# 08_BB_Processor.net
KiCad netlist of a schematic drawn in Altium Designer
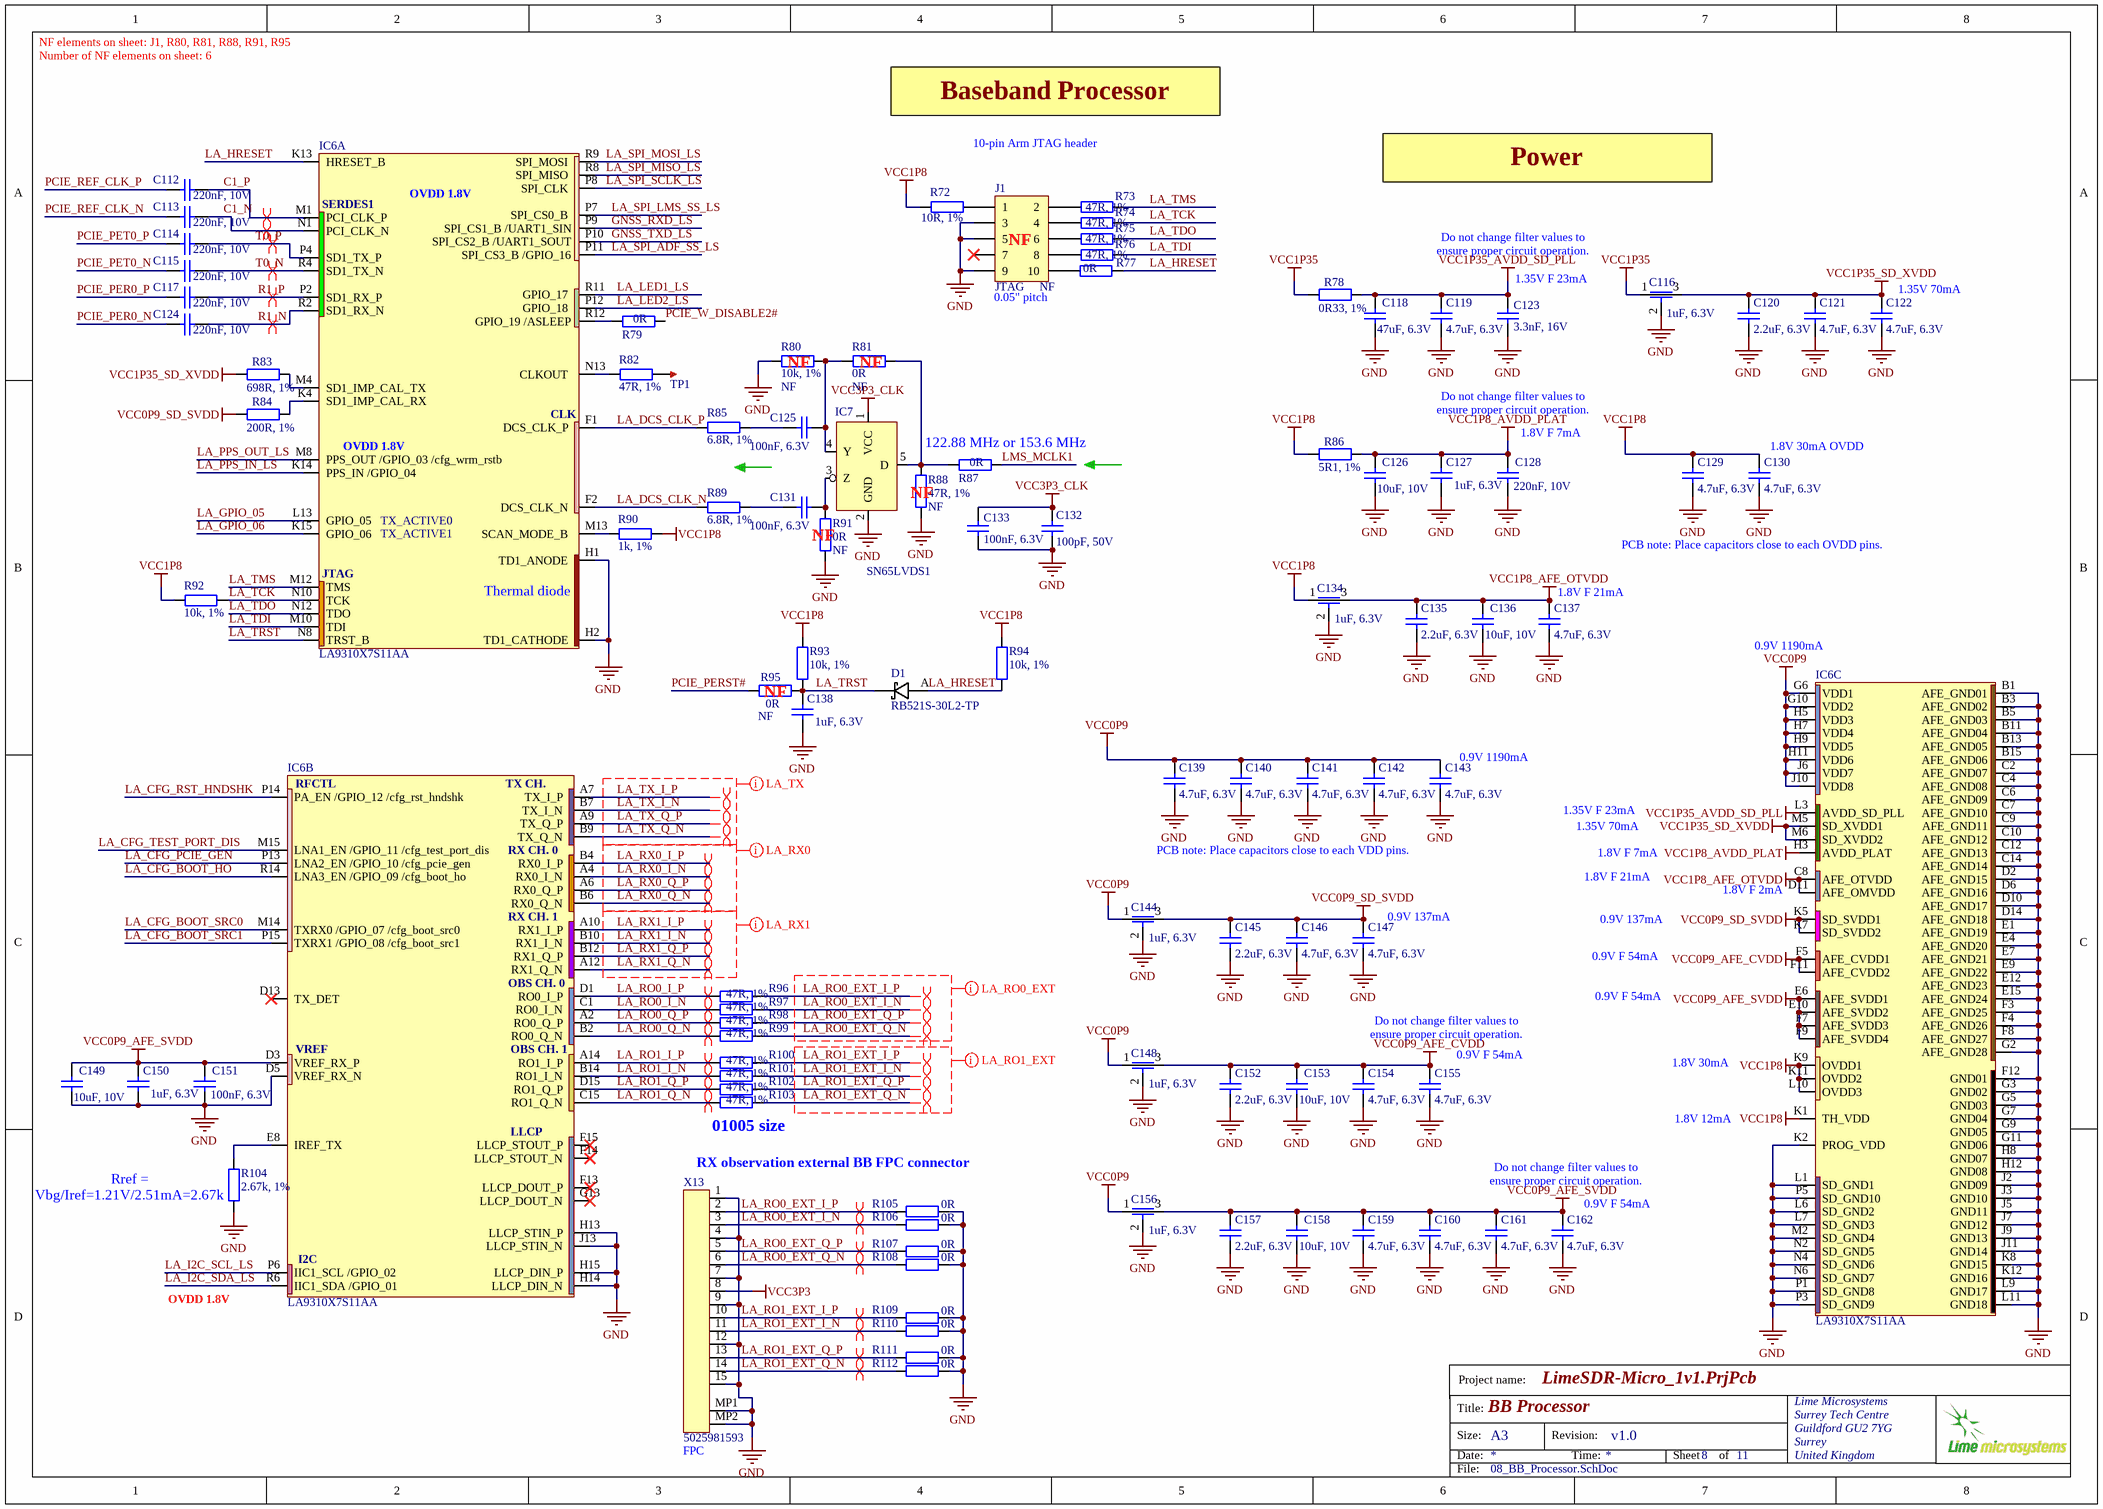
[diagram p0: 08_BB_Processor.SchDoc]

(export (version "E")
  (design (tool "Eeschema 10.0.6"))
  (components
    (comp (ref "C112")
      (value "220nF, 10V")
      (footprint "CAP0201")
      (fields
        (field (name "MANUFACTURER") "Murata")
        (field (name "TOLERANCE") "20%")
        (field (name "VOLTAGE") "10V")
      )
      (libsource (lib "LimeMicroAltiumLib_schLib") (part "Cap_0402"))
    )
    (comp (ref "C113")
      (value "220nF, 10V")
      (footprint "CAP0201")
      (fields
        (field (name "MANUFACTURER") "Murata")
        (field (name "TOLERANCE") "20%")
        (field (name "VOLTAGE") "10V")
      )
      (libsource (lib "LimeMicroAltiumLib_schLib") (part "Cap_0402"))
    )
    (comp (ref "C114")
      (value "220nF, 10V")
      (footprint "CAP0201")
      (fields
        (field (name "MANUFACTURER") "Murata")
        (field (name "TOLERANCE") "20%")
        (field (name "VOLTAGE") "10V")
      )
      (libsource (lib "LimeMicroAltiumLib_schLib") (part "Cap_0402"))
    )
    (comp (ref "C115")
      (value "220nF, 10V")
      (footprint "CAP0201")
      (fields
        (field (name "MANUFACTURER") "Murata")
        (field (name "TOLERANCE") "20%")
        (field (name "VOLTAGE") "10V")
      )
      (libsource (lib "LimeMicroAltiumLib_schLib") (part "Cap_0402"))
    )
    (comp (ref "C116")
      (value "1uF, 6.3V")
      (footprint "CAP0603_FEEDTHROUGH")
      (fields (field (name "MANUFACTURER") "TDK"))
      (libsource (lib "LimeMicroAltiumLib_schLib_r01") (part "Cap_feed_through"))
    )
    (comp (ref "C117")
      (value "220nF, 10V")
      (footprint "CAP0201")
      (fields
        (field (name "MANUFACTURER") "Murata")
        (field (name "TOLERANCE") "20%")
        (field (name "VOLTAGE") "10V")
      )
      (libsource (lib "LimeMicroAltiumLib_schLib") (part "Cap_0402"))
    )
    (comp (ref "C118")
      (value "47uF, 6.3V")
      (footprint "CAP0603")
      (fields (field (name "MANUFACTURER") "Murata") (field (name "TOLERANCE") "20%"))
      (libsource (lib "LimeFPGAboard_schLib") (part "Cap_0603"))
    )
    (comp (ref "C119")
      (value "4.7uF, 6.3V")
      (footprint "CAP0201")
      (fields (field (name "MANUFACTURER") "Murata") (field (name "TOLERANCE") "20%"))
      (libsource (lib "LimeMicroAltiumLib_schLib") (part "Cap_0402"))
    )
    (comp (ref "C120")
      (value "2.2uF, 6.3V")
      (footprint "CAP0201")
      (fields (field (name "MANUFACTURER") "Murata") (field (name "TOLERANCE") "20%"))
      (libsource (lib "LimeMicroAltiumLib_schLib") (part "Cap_0402"))
    )
    (comp (ref "C121")
      (value "4.7uF, 6.3V")
      (footprint "CAP0201")
      (fields (field (name "MANUFACTURER") "Murata") (field (name "TOLERANCE") "20%"))
      (libsource (lib "LimeMicroAltiumLib_schLib") (part "Cap_0402"))
    )
    (comp (ref "C122")
      (value "4.7uF, 6.3V")
      (footprint "CAP0201")
      (fields (field (name "MANUFACTURER") "Murata") (field (name "TOLERANCE") "20%"))
      (libsource (lib "LimeMicroAltiumLib_schLib") (part "Cap_0402"))
    )
    (comp (ref "C123")
      (value "3.3nF, 16V")
      (footprint "CAP0201")
      (description "Multilayer Ceramic Capacitor, 3300 pF, 16 V, ± 10%, X7R, 0201 [0603 Metric]")
      (fields (field (name "MANUFACTURER") "Murata"))
      (libsource (lib "LimeMicroAltiumLib_schLib") (part "Cap_0402"))
    )
    (comp (ref "C124")
      (value "220nF, 10V")
      (footprint "CAP0201")
      (fields
        (field (name "MANUFACTURER") "Murata")
        (field (name "TOLERANCE") "20%")
        (field (name "VOLTAGE") "10V")
      )
      (libsource (lib "LimeMicroAltiumLib_schLib") (part "Cap_0402"))
    )
    (comp (ref "C125")
      (value "100nF, 6.3V")
      (footprint "CAP0201")
      (fields (field (name "MANUFACTURER") "Samsung") (field (name "TOLERANCE") "20%"))
      (libsource (lib "LimeMicroAltiumLib_schLib") (part "Cap_0402"))
    )
    (comp (ref "C126")
      (value "10uF, 10V")
      (footprint "CAP0402")
      (fields (field (name "MANUFACTURER") "Murata"))
      (libsource (lib "LimeFPGAboard_schLib") (part "Cap_0603"))
    )
    (comp (ref "C127")
      (value "1uF, 6.3V")
      (footprint "CAP0201")
      (fields (field (name "TOLERANCE") "±20%") (field (name "MANUFACTURER") "TDK Corporation"))
      (libsource (lib "LimeMicroAltiumLib_schLib") (part "Cap_0402"))
    )
    (comp (ref "C128")
      (value "220nF, 10V")
      (footprint "CAP0201")
      (fields
        (field (name "MANUFACTURER") "Murata")
        (field (name "TOLERANCE") "20%")
        (field (name "VOLTAGE") "10V")
      )
      (libsource (lib "LimeMicroAltiumLib_schLib") (part "Cap_0402"))
    )
    (comp (ref "C129")
      (value "4.7uF, 6.3V")
      (footprint "CAP0201")
      (fields (field (name "MANUFACTURER") "Murata") (field (name "TOLERANCE") "20%"))
      (libsource (lib "LimeMicroAltiumLib_schLib") (part "Cap_0402"))
    )
    (comp (ref "C130")
      (value "4.7uF, 6.3V")
      (footprint "CAP0201")
      (fields (field (name "MANUFACTURER") "Murata") (field (name "TOLERANCE") "20%"))
      (libsource (lib "LimeMicroAltiumLib_schLib") (part "Cap_0402"))
    )
    (comp (ref "C131")
      (value "100nF, 6.3V")
      (footprint "CAP0201")
      (fields (field (name "MANUFACTURER") "Samsung") (field (name "TOLERANCE") "20%"))
      (libsource (lib "LimeMicroAltiumLib_schLib") (part "Cap_0402"))
    )
    (comp (ref "C132")
      (value "100pF, 50V")
      (footprint "CAP0201")
      (fields
        (field (name "MANUFACTURER") "TDK")
        (field (name "TOLERANCE") "5%")
        (field (name "VOLTAGE") "50V")
      )
      (libsource (lib "LimeMicroAltiumLib_schLib") (part "Cap_0402"))
    )
    (comp (ref "C133")
      (value "100nF, 6.3V")
      (footprint "CAP0201")
      (fields (field (name "MANUFACTURER") "Samsung") (field (name "TOLERANCE") "20%"))
      (libsource (lib "LimeMicroAltiumLib_schLib") (part "Cap_0402"))
    )
    (comp (ref "C134")
      (value "1uF, 6.3V")
      (footprint "CAP0603_FEEDTHROUGH")
      (fields (field (name "MANUFACTURER") "TDK"))
      (libsource (lib "LimeMicroAltiumLib_schLib_r01") (part "Cap_feed_through"))
    )
    (comp (ref "C135")
      (value "2.2uF, 6.3V")
      (footprint "CAP0201")
      (fields (field (name "MANUFACTURER") "Murata") (field (name "TOLERANCE") "20%"))
      (libsource (lib "LimeMicroAltiumLib_schLib") (part "Cap_0402"))
    )
    (comp (ref "C136")
      (value "10uF, 10V")
      (footprint "CAP0402")
      (fields (field (name "MANUFACTURER") "Murata"))
      (libsource (lib "LimeFPGAboard_schLib") (part "Cap_0603"))
    )
    (comp (ref "C137")
      (value "4.7uF, 6.3V")
      (footprint "CAP0201")
      (fields (field (name "MANUFACTURER") "Murata") (field (name "TOLERANCE") "20%"))
      (libsource (lib "LimeMicroAltiumLib_schLib") (part "Cap_0402"))
    )
    (comp (ref "C138")
      (value "1uF, 6.3V")
      (footprint "CAP0201")
      (fields (field (name "TOLERANCE") "±20%") (field (name "MANUFACTURER") "TDK Corporation"))
      (libsource (lib "LimeMicroAltiumLib_schLib") (part "Cap_0402"))
    )
    (comp (ref "C139")
      (value "4.7uF, 6.3V")
      (footprint "CAP0201")
      (fields (field (name "MANUFACTURER") "Murata") (field (name "TOLERANCE") "20%"))
      (libsource (lib "LimeMicroAltiumLib_schLib") (part "Cap_0402"))
    )
    (comp (ref "C140")
      (value "4.7uF, 6.3V")
      (footprint "CAP0201")
      (fields (field (name "MANUFACTURER") "Murata") (field (name "TOLERANCE") "20%"))
      (libsource (lib "LimeMicroAltiumLib_schLib") (part "Cap_0402"))
    )
    (comp (ref "C141")
      (value "4.7uF, 6.3V")
      (footprint "CAP0201")
      (fields (field (name "MANUFACTURER") "Murata") (field (name "TOLERANCE") "20%"))
      (libsource (lib "LimeMicroAltiumLib_schLib") (part "Cap_0402"))
    )
    (comp (ref "C142")
      (value "4.7uF, 6.3V")
      (footprint "CAP0201")
      (fields (field (name "MANUFACTURER") "Murata") (field (name "TOLERANCE") "20%"))
      (libsource (lib "LimeMicroAltiumLib_schLib") (part "Cap_0402"))
    )
    (comp (ref "C143")
      (value "4.7uF, 6.3V")
      (footprint "CAP0201")
      (fields (field (name "MANUFACTURER") "Murata") (field (name "TOLERANCE") "20%"))
      (libsource (lib "LimeMicroAltiumLib_schLib") (part "Cap_0402"))
    )
    (comp (ref "C144")
      (value "1uF, 6.3V")
      (footprint "CAP0603_FEEDTHROUGH")
      (fields (field (name "MANUFACTURER") "TDK"))
      (libsource (lib "LimeMicroAltiumLib_schLib_r01") (part "Cap_feed_through"))
    )
    (comp (ref "C145")
      (value "2.2uF, 6.3V")
      (footprint "CAP0201")
      (fields (field (name "MANUFACTURER") "Murata") (field (name "TOLERANCE") "20%"))
      (libsource (lib "LimeMicroAltiumLib_schLib") (part "Cap_0402"))
    )
    (comp (ref "C146")
      (value "4.7uF, 6.3V")
      (footprint "CAP0201")
      (fields (field (name "MANUFACTURER") "Murata") (field (name "TOLERANCE") "20%"))
      (libsource (lib "LimeMicroAltiumLib_schLib") (part "Cap_0402"))
    )
    (comp (ref "C147")
      (value "4.7uF, 6.3V")
      (footprint "CAP0201")
      (fields (field (name "MANUFACTURER") "Murata") (field (name "TOLERANCE") "20%"))
      (libsource (lib "LimeMicroAltiumLib_schLib") (part "Cap_0402"))
    )
    (comp (ref "C148")
      (value "1uF, 6.3V")
      (footprint "CAP0603_FEEDTHROUGH")
      (fields (field (name "MANUFACTURER") "TDK"))
      (libsource (lib "LimeMicroAltiumLib_schLib_r01") (part "Cap_feed_through"))
    )
    (comp (ref "C149")
      (value "10uF, 10V")
      (footprint "CAP0402")
      (fields (field (name "MANUFACTURER") "Murata"))
      (libsource (lib "LimeFPGAboard_schLib") (part "Cap_0603"))
    )
    (comp (ref "C150")
      (value "1uF, 6.3V")
      (footprint "CAP0201")
      (fields (field (name "TOLERANCE") "±20%") (field (name "MANUFACTURER") "TDK Corporation"))
      (libsource (lib "LimeMicroAltiumLib_schLib") (part "Cap_0402"))
    )
    (comp (ref "C151")
      (value "100nF, 6.3V")
      (footprint "CAP0201")
      (fields (field (name "MANUFACTURER") "Samsung") (field (name "TOLERANCE") "20%"))
      (libsource (lib "LimeMicroAltiumLib_schLib") (part "Cap_0402"))
    )
    (comp (ref "C152")
      (value "2.2uF, 6.3V")
      (footprint "CAP0201")
      (fields (field (name "MANUFACTURER") "Murata") (field (name "TOLERANCE") "20%"))
      (libsource (lib "LimeMicroAltiumLib_schLib") (part "Cap_0402"))
    )
    (comp (ref "C153")
      (value "10uF, 10V")
      (footprint "CAP0402")
      (fields (field (name "MANUFACTURER") "Murata"))
      (libsource (lib "LimeFPGAboard_schLib") (part "Cap_0603"))
    )
    (comp (ref "C154")
      (value "4.7uF, 6.3V")
      (footprint "CAP0201")
      (fields (field (name "MANUFACTURER") "Murata") (field (name "TOLERANCE") "20%"))
      (libsource (lib "LimeMicroAltiumLib_schLib") (part "Cap_0402"))
    )
    (comp (ref "C155")
      (value "4.7uF, 6.3V")
      (footprint "CAP0201")
      (fields (field (name "MANUFACTURER") "Murata") (field (name "TOLERANCE") "20%"))
      (libsource (lib "LimeMicroAltiumLib_schLib") (part "Cap_0402"))
    )
    (comp (ref "C156")
      (value "1uF, 6.3V")
      (footprint "CAP0603_FEEDTHROUGH")
      (fields (field (name "MANUFACTURER") "TDK"))
      (libsource (lib "LimeMicroAltiumLib_schLib_r01") (part "Cap_feed_through"))
    )
    (comp (ref "C157")
      (value "2.2uF, 6.3V")
      (footprint "CAP0201")
      (fields (field (name "MANUFACTURER") "Murata") (field (name "TOLERANCE") "20%"))
      (libsource (lib "LimeMicroAltiumLib_schLib") (part "Cap_0402"))
    )
    (comp (ref "C158")
      (value "10uF, 10V")
      (footprint "CAP0402")
      (fields (field (name "MANUFACTURER") "Murata"))
      (libsource (lib "LimeFPGAboard_schLib") (part "Cap_0603"))
    )
    (comp (ref "C159")
      (value "4.7uF, 6.3V")
      (footprint "CAP0201")
      (fields (field (name "MANUFACTURER") "Murata") (field (name "TOLERANCE") "20%"))
      (libsource (lib "LimeMicroAltiumLib_schLib") (part "Cap_0402"))
    )
    (comp (ref "C160")
      (value "4.7uF, 6.3V")
      (footprint "CAP0201")
      (fields (field (name "MANUFACTURER") "Murata") (field (name "TOLERANCE") "20%"))
      (libsource (lib "LimeMicroAltiumLib_schLib") (part "Cap_0402"))
    )
    (comp (ref "C161")
      (value "4.7uF, 6.3V")
      (footprint "CAP0201")
      (fields (field (name "MANUFACTURER") "Murata") (field (name "TOLERANCE") "20%"))
      (libsource (lib "LimeMicroAltiumLib_schLib") (part "Cap_0402"))
    )
    (comp (ref "C162")
      (value "4.7uF, 6.3V")
      (footprint "CAP0201")
      (fields (field (name "MANUFACTURER") "Murata") (field (name "TOLERANCE") "20%"))
      (libsource (lib "LimeMicroAltiumLib_schLib") (part "Cap_0402"))
    )
    (comp (ref "D1")
      (value "RB521S-30L2-TP")
      (footprint "RB521S-30L2-TP_DFN1006")
      (fields (field (name "MANUFACTURER") "MCC"))
      (libsource (lib "LimeMicroAltiumLib") (part "BAT46JFILM_shottky_diode"))
    )
    (comp (ref "IC6")
      (value "LA9310X7S11AA")
      (footprint "LA9310X7S11AA")
      (fields (field (name "MANUFACTURER") "NXP Semiconductors"))
      (libsource (lib "LimeMicroAltiumLib") (part "LA9310X7S11AA"))
    )
    (comp (ref "IC7")
      (value "SN65LVDS1")
      (footprint "SOT23-5_NO_SILK")
      (fields (field (name "MANUFACTURER") "TEXAS INSTRUMENTS"))
      (libsource (lib "LimeMicroAltiumLib_schLib") (part "SN65LVDS1"))
    )
    (comp (ref "J1")
      (value "JTAG")
      (footprint "HEADER_5x2_TH_HALF_PITCH")
      (description "Header, 5-Pin, Dual row")
      (fields (field (name "ASSEMBLY INFO") "NF") (field (name "MANUFACTURER") "Adam Equipment"))
      (libsource (lib "LimeMicroAltiumLib") (part "Header 5X2_SWD"))
    )
    (comp (ref "R72")
      (value "10R, 1%")
      (footprint "RES0201")
      (fields
        (field (name "MANUFACTURER") "Panasonic Electronic Components")
        (field (name "TOLERANCE") "±1%")
      )
      (libsource (lib "LimeMicroAltiumLib_schLib") (part "Res_0402"))
    )
    (comp (ref "R73")
      (value "47R, 1%")
      (footprint "RES0201")
      (fields (field (name "MANUFACTURER") "Yageo") (field (name "TOLERANCE") "1%"))
      (libsource (lib "LimeFPGAboard_schLib") (part "Res_0402"))
    )
    (comp (ref "R74")
      (value "47R, 1%")
      (footprint "RES0201")
      (fields (field (name "MANUFACTURER") "Yageo") (field (name "TOLERANCE") "1%"))
      (libsource (lib "LimeFPGAboard_schLib") (part "Res_0402"))
    )
    (comp (ref "R75")
      (value "47R, 1%")
      (footprint "RES0201")
      (fields (field (name "MANUFACTURER") "Yageo") (field (name "TOLERANCE") "1%"))
      (libsource (lib "LimeFPGAboard_schLib") (part "Res_0402"))
    )
    (comp (ref "R76")
      (value "47R, 1%")
      (footprint "RES0201")
      (fields (field (name "MANUFACTURER") "Yageo") (field (name "TOLERANCE") "1%"))
      (libsource (lib "LimeFPGAboard_schLib") (part "Res_0402"))
    )
    (comp (ref "R77")
      (value "0R")
      (footprint "RES0201")
      (fields (field (name "MANUFACTURER") "Yageo") (field (name "TOLERANCE") "5%"))
      (libsource (lib "LimeFPGAboard_schLib") (part "Res_0402"))
    )
    (comp (ref "R78")
      (value "0R33, 1%")
      (footprint "RES0201")
      (fields (field (name "MANUFACTURER") "Ohmite"))
      (libsource (lib "LimeFPGAboard_schLib") (part "Res_0402"))
    )
    (comp (ref "R79")
      (value "0R")
      (footprint "RES0201")
      (fields (field (name "MANUFACTURER") "Yageo") (field (name "TOLERANCE") "5%"))
      (libsource (lib "LimeFPGAboard_schLib") (part "Res_0402"))
    )
    (comp (ref "R80")
      (value "10k, 1%")
      (footprint "RES0201")
      (fields
        (field (name "ASSEMBLY INFO") "NF")
        (field (name "MANUFACTURER") "Yageo")
        (field (name "TOLERANCE") "1%")
      )
      (libsource (lib "LimeFPGAboard_schLib") (part "Res_0402"))
    )
    (comp (ref "R81")
      (value "0R")
      (footprint "RES0201")
      (fields
        (field (name "ASSEMBLY INFO") "NF")
        (field (name "MANUFACTURER") "Yageo")
        (field (name "TOLERANCE") "5%")
      )
      (libsource (lib "LimeFPGAboard_schLib") (part "Res_0402"))
    )
    (comp (ref "R82")
      (value "47R, 1%")
      (footprint "RES0201")
      (fields (field (name "MANUFACTURER") "Yageo") (field (name "TOLERANCE") "1%"))
      (libsource (lib "LimeFPGAboard_schLib") (part "Res_0402"))
    )
    (comp (ref "R83")
      (value "698R, 1%")
      (footprint "RES0201")
      (fields (field (name "MANUFACTURER") "Yageo") (field (name "TOLERANCE") "1%"))
      (libsource (lib "LimeFPGAboard_schLib") (part "Res_0402"))
    )
    (comp (ref "R84")
      (value "200R, 1%")
      (footprint "RES0201")
      (fields (field (name "MANUFACTURER") "Yageo") (field (name "TOLERANCE") "1%"))
      (libsource (lib "LimeFPGAboard_schLib") (part "Res_0402"))
    )
    (comp (ref "R85")
      (value "6.8R, 1%")
      (footprint "RES0201")
      (fields (field (name "MANUFACTURER") "Yageo") (field (name "TOLERANCE") "1%"))
      (libsource (lib "LimeMicroAltiumLib_schLib") (part "Res_0402"))
    )
    (comp (ref "R86")
      (value "5R1, 1%")
      (footprint "RES0201")
      (fields (field (name "MANUFACTURER") "Yageo"))
      (libsource (lib "LimeFPGAboard_schLib") (part "Res_0402"))
    )
    (comp (ref "R87")
      (value "0R")
      (footprint "RES0201")
      (fields (field (name "MANUFACTURER") "Yageo") (field (name "TOLERANCE") "5%"))
      (libsource (lib "LimeFPGAboard_schLib") (part "Res_0402"))
    )
    (comp (ref "R88")
      (value "47R, 1%")
      (footprint "RES0201")
      (fields
        (field (name "ASSEMBLY INFO") "NF")
        (field (name "MANUFACTURER") "Yageo")
        (field (name "TOLERANCE") "1%")
      )
      (libsource (lib "LimeFPGAboard_schLib") (part "Res_0402"))
    )
    (comp (ref "R89")
      (value "6.8R, 1%")
      (footprint "RES0201")
      (fields (field (name "MANUFACTURER") "Yageo") (field (name "TOLERANCE") "1%"))
      (libsource (lib "LimeMicroAltiumLib_schLib") (part "Res_0402"))
    )
    (comp (ref "R90")
      (value "1k, 1%")
      (footprint "RES0201")
      (fields (field (name "MANUFACTURER") "Yageo") (field (name "TOLERANCE") "1%"))
      (libsource (lib "LimeMicroAltiumLib_schLib") (part "Res_0402"))
    )
    (comp (ref "R91")
      (value "0R")
      (footprint "RES0201")
      (fields
        (field (name "ASSEMBLY INFO") "NF")
        (field (name "MANUFACTURER") "Yageo")
        (field (name "TOLERANCE") "5%")
      )
      (libsource (lib "LimeFPGAboard_schLib") (part "Res_0402"))
    )
    (comp (ref "R92")
      (value "10k, 1%")
      (footprint "RES0201")
      (fields (field (name "MANUFACTURER") "Yageo") (field (name "TOLERANCE") "1%"))
      (libsource (lib "LimeFPGAboard_schLib") (part "Res_0402"))
    )
    (comp (ref "R93")
      (value "10k, 1%")
      (footprint "RES0201")
      (fields (field (name "MANUFACTURER") "Yageo") (field (name "TOLERANCE") "1%"))
      (libsource (lib "LimeFPGAboard_schLib") (part "Res_0402"))
    )
    (comp (ref "R94")
      (value "10k, 1%")
      (footprint "RES0201")
      (fields (field (name "MANUFACTURER") "Yageo") (field (name "TOLERANCE") "1%"))
      (libsource (lib "LimeFPGAboard_schLib") (part "Res_0402"))
    )
    (comp (ref "R95")
      (value "0R")
      (footprint "RES0201")
      (fields
        (field (name "ASSEMBLY INFO") "NF")
        (field (name "MANUFACTURER") "Yageo")
        (field (name "TOLERANCE") "5%")
      )
      (libsource (lib "LimeFPGAboard_schLib") (part "Res_0402"))
    )
    (comp (ref "R96")
      (value "47R, 1%")
      (footprint "RES01005")
      (fields (field (name "MANUFACTURER") "Yageo") (field (name "TOLERANCE") "1%"))
      (libsource (lib "LimeFPGAboard_schLib") (part "Res_0402"))
    )
    (comp (ref "R97")
      (value "47R, 1%")
      (footprint "RES01005")
      (fields (field (name "MANUFACTURER") "Yageo") (field (name "TOLERANCE") "1%"))
      (libsource (lib "LimeFPGAboard_schLib") (part "Res_0402"))
    )
    (comp (ref "R98")
      (value "47R, 1%")
      (footprint "RES01005")
      (fields (field (name "MANUFACTURER") "Yageo") (field (name "TOLERANCE") "1%"))
      (libsource (lib "LimeFPGAboard_schLib") (part "Res_0402"))
    )
    (comp (ref "R99")
      (value "47R, 1%")
      (footprint "RES01005")
      (fields (field (name "MANUFACTURER") "Yageo") (field (name "TOLERANCE") "1%"))
      (libsource (lib "LimeFPGAboard_schLib") (part "Res_0402"))
    )
    (comp (ref "R100")
      (value "47R, 1%")
      (footprint "RES01005")
      (fields (field (name "MANUFACTURER") "Yageo") (field (name "TOLERANCE") "1%"))
      (libsource (lib "LimeFPGAboard_schLib") (part "Res_0402"))
    )
    (comp (ref "R101")
      (value "47R, 1%")
      (footprint "RES01005")
      (fields (field (name "MANUFACTURER") "Yageo") (field (name "TOLERANCE") "1%"))
      (libsource (lib "LimeFPGAboard_schLib") (part "Res_0402"))
    )
    (comp (ref "R102")
      (value "47R, 1%")
      (footprint "RES01005")
      (fields (field (name "MANUFACTURER") "Yageo") (field (name "TOLERANCE") "1%"))
      (libsource (lib "LimeFPGAboard_schLib") (part "Res_0402"))
    )
    (comp (ref "R103")
      (value "47R, 1%")
      (footprint "RES01005")
      (fields (field (name "MANUFACTURER") "Yageo") (field (name "TOLERANCE") "1%"))
      (libsource (lib "LimeFPGAboard_schLib") (part "Res_0402"))
    )
    (comp (ref "R104")
      (value "2.67k, 1%")
      (footprint "RES0201")
      (fields (field (name "MANUFACTURER") "Stackpole Electronics") (field (name "TOLERANCE") "1%"))
      (libsource (lib "LimeFPGAboard_schLib") (part "Res_0402"))
    )
    (comp (ref "R105")
      (value "0R")
      (footprint "RES01005")
      (fields (field (name "MANUFACTURER") "Panasonic") (field (name "TOLERANCE") "5%"))
      (libsource (lib "LimeFPGAboard_schLib") (part "Res_0402"))
    )
    (comp (ref "R106")
      (value "0R")
      (footprint "RES01005")
      (fields (field (name "MANUFACTURER") "Panasonic") (field (name "TOLERANCE") "5%"))
      (libsource (lib "LimeFPGAboard_schLib") (part "Res_0402"))
    )
    (comp (ref "R107")
      (value "0R")
      (footprint "RES01005")
      (fields (field (name "MANUFACTURER") "Panasonic") (field (name "TOLERANCE") "5%"))
      (libsource (lib "LimeFPGAboard_schLib") (part "Res_0402"))
    )
    (comp (ref "R108")
      (value "0R")
      (footprint "RES01005")
      (fields (field (name "MANUFACTURER") "Panasonic") (field (name "TOLERANCE") "5%"))
      (libsource (lib "LimeFPGAboard_schLib") (part "Res_0402"))
    )
    (comp (ref "R109")
      (value "0R")
      (footprint "RES01005")
      (fields (field (name "MANUFACTURER") "Panasonic") (field (name "TOLERANCE") "5%"))
      (libsource (lib "LimeFPGAboard_schLib") (part "Res_0402"))
    )
    (comp (ref "R110")
      (value "0R")
      (footprint "RES01005")
      (fields (field (name "MANUFACTURER") "Panasonic") (field (name "TOLERANCE") "5%"))
      (libsource (lib "LimeFPGAboard_schLib") (part "Res_0402"))
    )
    (comp (ref "R111")
      (value "0R")
      (footprint "RES01005")
      (fields (field (name "MANUFACTURER") "Panasonic") (field (name "TOLERANCE") "5%"))
      (libsource (lib "LimeFPGAboard_schLib") (part "Res_0402"))
    )
    (comp (ref "R112")
      (value "0R")
      (footprint "RES01005")
      (fields (field (name "MANUFACTURER") "Panasonic") (field (name "TOLERANCE") "5%"))
      (libsource (lib "LimeFPGAboard_schLib") (part "Res_0402"))
    )
    (comp (ref "TP1")
      (value "TESTPOINT_PAD")
      (footprint "TP_PAD_1MM")
      (description "Test Point PCB mount Miniature White")
      (libsource (lib "LimeMicroAltiumLib_schLib_r04") (part "TESTPOINT_PAD"))
    )
    (comp (ref "X13")
      (value "5025981593")
      (footprint "5025981593_FPC_connector")
      (fields (field (name "MANUFACTURER") "Molex"))
      (libsource (lib "LimeMicroAltiumLib_schLib_r04") (part "5025981593_FPC_connector"))
    )
  )
  (nets
    (net (code "1") (name "/C1_N") (class "Default")
      (node (ref "C113") (pin "2") (pinfunction "2_2") (pintype "passive"))
      (node (ref "IC6") (pin "N1") (pinfunction "PCI_CLK_N_N1") (pintype "power_in"))
    )
    (net (code "2") (name "/C1_P") (class "Default")
      (node (ref "C112") (pin "2") (pinfunction "2_2") (pintype "passive"))
      (node (ref "IC6") (pin "M1") (pinfunction "PCI_CLK_P_M1") (pintype "power_in"))
    )
    (net (code "3") (name "/GNSS_RXD_LS") (class "Default")
      (node (ref "IC6") (pin "P9") (pinfunction "SPI_CS1_B_/UART1_SIN_P9") (pintype "power_in"))
    )
    (net (code "4") (name "/GNSS_TXD_LS") (class "Default")
      (node (ref "IC6") (pin "P10") (pinfunction "SPI_CS2_B_/UART1_SOUT_P10") (pintype "power_in"))
    )
    (net (code "5") (name "/LA_CFG_BOOT_HO") (class "Default")
      (node (ref "IC6") (pin "R14") (pinfunction "LNA3_EN_/GPIO_09_/cfg_boot_ho_R14") (pintype "power_in"))
    )
    (net (code "6") (name "/LA_CFG_BOOT_SRC0") (class "Default")
      (node (ref "IC6") (pin "M14") (pinfunction "TXRX0_/GPIO_07_/cfg_boot_src0_M14") (pintype "power_in"))
    )
    (net (code "7") (name "/LA_CFG_BOOT_SRC1") (class "Default")
      (node (ref "IC6") (pin "P15") (pinfunction "TXRX1_/GPIO_08_/cfg_boot_src1_P15") (pintype "power_in"))
    )
    (net (code "8") (name "/LA_CFG_PCIE_GEN") (class "Default")
      (node (ref "IC6") (pin "P13") (pinfunction "LNA2_EN_/GPIO_10_/cfg_pcie_gen_P13") (pintype "power_in"))
    )
    (net (code "9") (name "/LA_CFG_RST_HNDSHK") (class "Default")
      (node (ref "IC6") (pin "P14") (pinfunction "PA_EN_/GPIO_12_/cfg_rst_hndshk_P14") (pintype "power_in"))
    )
    (net (code "10") (name "/LA_CFG_TEST_PORT_DIS") (class "Default")
      (node (ref "IC6") (pin "M15") (pinfunction "LNA1_EN_/GPIO_11_/cfg_test_port_dis_M15") (pintype "power_in"))
    )
    (net (code "11") (name "/LA_DCS_CLK_N") (class "Default")
      (node (ref "IC6") (pin "F2") (pinfunction "DCS_CLK_N_F2") (pintype "power_in"))
      (node (ref "R89") (pin "2") (pinfunction "2_2") (pintype "passive"))
    )
    (net (code "12") (name "/LA_DCS_CLK_P") (class "Default")
      (node (ref "IC6") (pin "F1") (pinfunction "DCS_CLK_P_F1") (pintype "power_in"))
      (node (ref "R85") (pin "2") (pinfunction "2_2") (pintype "passive"))
    )
    (net (code "13") (name "/LA_GPIO_05") (class "Default")
      (node (ref "IC6") (pin "L13") (pinfunction "GPIO_05_L13") (pintype "power_in"))
    )
    (net (code "14") (name "/LA_GPIO_06") (class "Default")
      (node (ref "IC6") (pin "K15") (pinfunction "GPIO_06_K15") (pintype "power_in"))
    )
    (net (code "15") (name "/LA_HRESET") (class "Default")
      (node (ref "D1") (pin "A") (pinfunction "A_A") (pintype "passive"))
      (node (ref "IC6") (pin "K13") (pinfunction "HRESET_B_K13") (pintype "power_in"))
      (node (ref "R77") (pin "2") (pinfunction "2_2") (pintype "passive"))
      (node (ref "R94") (pin "2") (pinfunction "2_2") (pintype "passive"))
    )
    (net (code "16") (name "/LA_I2C_SCL_LS") (class "Default")
      (node (ref "IC6") (pin "P6") (pinfunction "IIC1_SCL_/GPIO_02_P6") (pintype "power_in"))
    )
    (net (code "17") (name "/LA_I2C_SDA_LS") (class "Default")
      (node (ref "IC6") (pin "R6") (pinfunction "IIC1_SDA_/GPIO_01_R6") (pintype "power_in"))
    )
    (net (code "18") (name "/LA_LED1_LS") (class "Default")
      (node (ref "IC6") (pin "R11") (pinfunction "GPIO_17_R11") (pintype "power_in"))
    )
    (net (code "19") (name "/LA_LED2_LS") (class "Default")
      (node (ref "IC6") (pin "P12") (pinfunction "GPIO_18_P12") (pintype "power_in"))
    )
    (net (code "20") (name "/LA_PPS_IN_LS") (class "Default")
      (node (ref "IC6") (pin "K14") (pinfunction "PPS_IN_/GPIO_04_K14") (pintype "power_in"))
    )
    (net (code "21") (name "/LA_PPS_OUT_LS") (class "Default")
      (node (ref "IC6") (pin "M8") (pinfunction "PPS_OUT_/GPIO_03_/cfg_wrm_rstb_M8") (pintype "power_in"))
    )
    (net (code "22") (name "/LA_RO0_EXT_I_N") (class "Default")
      (node (ref "R106") (pin "1") (pinfunction "1_1") (pintype "passive"))
      (node (ref "R97") (pin "2") (pinfunction "2_2") (pintype "passive"))
      (node (ref "X13") (pin "3") (pinfunction "3_3") (pintype "passive"))
    )
    (net (code "23") (name "/LA_RO0_EXT_I_P") (class "Default")
      (node (ref "R105") (pin "1") (pinfunction "1_1") (pintype "passive"))
      (node (ref "R96") (pin "2") (pinfunction "2_2") (pintype "passive"))
      (node (ref "X13") (pin "2") (pinfunction "2_2") (pintype "passive"))
    )
    (net (code "24") (name "/LA_RO0_EXT_Q_N") (class "Default")
      (node (ref "R108") (pin "1") (pinfunction "1_1") (pintype "passive"))
      (node (ref "R99") (pin "2") (pinfunction "2_2") (pintype "passive"))
      (node (ref "X13") (pin "6") (pinfunction "6_6") (pintype "passive"))
    )
    (net (code "25") (name "/LA_RO0_EXT_Q_P") (class "Default")
      (node (ref "R107") (pin "1") (pinfunction "1_1") (pintype "passive"))
      (node (ref "R98") (pin "2") (pinfunction "2_2") (pintype "passive"))
      (node (ref "X13") (pin "5") (pinfunction "5_5") (pintype "passive"))
    )
    (net (code "26") (name "/LA_RO0_I_N") (class "Default")
      (node (ref "IC6") (pin "C1") (pinfunction "RO0_I_N_C1") (pintype "power_in"))
      (node (ref "R97") (pin "1") (pinfunction "1_1") (pintype "passive"))
    )
    (net (code "27") (name "/LA_RO0_I_P") (class "Default")
      (node (ref "IC6") (pin "D1") (pinfunction "RO0_I_P_D1") (pintype "power_in"))
      (node (ref "R96") (pin "1") (pinfunction "1_1") (pintype "passive"))
    )
    (net (code "28") (name "/LA_RO0_Q_N") (class "Default")
      (node (ref "IC6") (pin "B2") (pinfunction "RO0_Q_N_B2") (pintype "power_in"))
      (node (ref "R99") (pin "1") (pinfunction "1_1") (pintype "passive"))
    )
    (net (code "29") (name "/LA_RO0_Q_P") (class "Default")
      (node (ref "IC6") (pin "A2") (pinfunction "RO0_Q_P_A2") (pintype "power_in"))
      (node (ref "R98") (pin "1") (pinfunction "1_1") (pintype "passive"))
    )
    (net (code "30") (name "/LA_RO1_EXT_I_N") (class "Default")
      (node (ref "R101") (pin "2") (pinfunction "2_2") (pintype "passive"))
      (node (ref "R110") (pin "1") (pinfunction "1_1") (pintype "passive"))
      (node (ref "X13") (pin "11") (pinfunction "11_11") (pintype "passive"))
    )
    (net (code "31") (name "/LA_RO1_EXT_I_P") (class "Default")
      (node (ref "R100") (pin "2") (pinfunction "2_2") (pintype "passive"))
      (node (ref "R109") (pin "1") (pinfunction "1_1") (pintype "passive"))
      (node (ref "X13") (pin "10") (pinfunction "10_10") (pintype "passive"))
    )
    (net (code "32") (name "/LA_RO1_EXT_Q_N") (class "Default")
      (node (ref "R103") (pin "2") (pinfunction "2_2") (pintype "passive"))
      (node (ref "R112") (pin "1") (pinfunction "1_1") (pintype "passive"))
      (node (ref "X13") (pin "14") (pinfunction "14_14") (pintype "passive"))
    )
    (net (code "33") (name "/LA_RO1_EXT_Q_P") (class "Default")
      (node (ref "R102") (pin "2") (pinfunction "2_2") (pintype "passive"))
      (node (ref "R111") (pin "1") (pinfunction "1_1") (pintype "passive"))
      (node (ref "X13") (pin "13") (pinfunction "13_13") (pintype "passive"))
    )
    (net (code "34") (name "/LA_RO1_I_N") (class "Default")
      (node (ref "IC6") (pin "B14") (pinfunction "RO1_I_N_B14") (pintype "power_in"))
      (node (ref "R101") (pin "1") (pinfunction "1_1") (pintype "passive"))
    )
    (net (code "35") (name "/LA_RO1_I_P") (class "Default")
      (node (ref "IC6") (pin "A14") (pinfunction "RO1_I_P_A14") (pintype "power_in"))
      (node (ref "R100") (pin "1") (pinfunction "1_1") (pintype "passive"))
    )
    (net (code "36") (name "/LA_RO1_Q_N") (class "Default")
      (node (ref "IC6") (pin "C15") (pinfunction "RO1_Q_N_C15") (pintype "power_in"))
      (node (ref "R103") (pin "1") (pinfunction "1_1") (pintype "passive"))
    )
    (net (code "37") (name "/LA_RO1_Q_P") (class "Default")
      (node (ref "IC6") (pin "D15") (pinfunction "RO1_Q_P_D15") (pintype "power_in"))
      (node (ref "R102") (pin "1") (pinfunction "1_1") (pintype "passive"))
    )
    (net (code "38") (name "/LA_RX0_I_N") (class "Default")
      (node (ref "IC6") (pin "A4") (pinfunction "RX0_I_N_A4") (pintype "power_in"))
    )
    (net (code "39") (name "/LA_RX0_I_P") (class "Default")
      (node (ref "IC6") (pin "B4") (pinfunction "RX0_I_P_B4") (pintype "power_in"))
    )
    (net (code "40") (name "/LA_RX0_Q_N") (class "Default")
      (node (ref "IC6") (pin "B6") (pinfunction "RX0_Q_N_B6") (pintype "power_in"))
    )
    (net (code "41") (name "/LA_RX0_Q_P") (class "Default")
      (node (ref "IC6") (pin "A6") (pinfunction "RX0_Q_P_A6") (pintype "power_in"))
    )
    (net (code "42") (name "/LA_RX1_I_N") (class "Default")
      (node (ref "IC6") (pin "B10") (pinfunction "RX1_I_N_B10") (pintype "power_in"))
    )
    (net (code "43") (name "/LA_RX1_I_P") (class "Default")
      (node (ref "IC6") (pin "A10") (pinfunction "RX1_I_P_A10") (pintype "power_in"))
    )
    (net (code "44") (name "/LA_RX1_Q_N") (class "Default")
      (node (ref "IC6") (pin "A12") (pinfunction "RX1_Q_N_A12") (pintype "power_in"))
    )
    (net (code "45") (name "/LA_RX1_Q_P") (class "Default")
      (node (ref "IC6") (pin "B12") (pinfunction "RX1_Q_P_B12") (pintype "power_in"))
    )
    (net (code "46") (name "/LA_SPI_ADF_SS_LS") (class "Default")
      (node (ref "IC6") (pin "P11") (pinfunction "SPI_CS3_B_/GPIO_16_P11") (pintype "power_in"))
    )
    (net (code "47") (name "/LA_SPI_LMS_SS_LS") (class "Default")
      (node (ref "IC6") (pin "P7") (pinfunction "SPI_CS0_B_P7") (pintype "power_in"))
    )
    (net (code "48") (name "/LA_SPI_MISO_LS") (class "Default")
      (node (ref "IC6") (pin "R8") (pinfunction "SPI_MISO_R8") (pintype "power_in"))
    )
    (net (code "49") (name "/LA_SPI_MOSI_LS") (class "Default")
      (node (ref "IC6") (pin "R9") (pinfunction "SPI_MOSI_R9") (pintype "power_in"))
    )
    (net (code "50") (name "/LA_SPI_SCLK_LS") (class "Default")
      (node (ref "IC6") (pin "P8") (pinfunction "SPI_CLK_P8") (pintype "power_in"))
    )
    (net (code "51") (name "/LA_TCK") (class "Default")
      (node (ref "IC6") (pin "N10") (pinfunction "TCK_N10") (pintype "power_in"))
      (node (ref "R74") (pin "1") (pinfunction "1_1") (pintype "passive"))
      (node (ref "R92") (pin "2") (pinfunction "2_2") (pintype "passive"))
    )
    (net (code "52") (name "/LA_TDI") (class "Default")
      (node (ref "IC6") (pin "M10") (pinfunction "TDI_M10") (pintype "power_in"))
      (node (ref "R76") (pin "1") (pinfunction "1_1") (pintype "passive"))
    )
    (net (code "53") (name "/LA_TDO") (class "Default")
      (node (ref "IC6") (pin "N12") (pinfunction "TDO_N12") (pintype "power_in"))
      (node (ref "R75") (pin "1") (pinfunction "1_1") (pintype "passive"))
    )
    (net (code "54") (name "/LA_TMS") (class "Default")
      (node (ref "IC6") (pin "M12") (pinfunction "TMS_M12") (pintype "power_in"))
      (node (ref "R73") (pin "1") (pinfunction "1_1") (pintype "passive"))
    )
    (net (code "55") (name "/LA_TRST") (class "Default")
      (node (ref "C138") (pin "1") (pinfunction "1_1") (pintype "passive"))
      (node (ref "D1") (pin "C") (pinfunction "C_C") (pintype "passive"))
      (node (ref "IC6") (pin "N8") (pinfunction "TRST_B_N8") (pintype "power_in"))
      (node (ref "R93") (pin "2") (pinfunction "2_2") (pintype "passive"))
      (node (ref "R95") (pin "2") (pinfunction "2_2") (pintype "passive"))
    )
    (net (code "56") (name "/LA_TX_I_N") (class "Default")
      (node (ref "IC6") (pin "B7") (pinfunction "TX_I_N_B7") (pintype "power_in"))
    )
    (net (code "57") (name "/LA_TX_I_P") (class "Default")
      (node (ref "IC6") (pin "A7") (pinfunction "TX_I_P_A7") (pintype "power_in"))
    )
    (net (code "58") (name "/LA_TX_Q_N") (class "Default")
      (node (ref "IC6") (pin "B9") (pinfunction "TX_Q_N_B9") (pintype "power_in"))
    )
    (net (code "59") (name "/LA_TX_Q_P") (class "Default")
      (node (ref "IC6") (pin "A9") (pinfunction "TX_Q_P_A9") (pintype "power_in"))
    )
    (net (code "60") (name "/LMS_MCLK1") (class "Default")
      (node (ref "R87") (pin "1") (pinfunction "1_1") (pintype "passive"))
    )
    (net (code "61") (name "/PCIE_PER0_N") (class "Default")
      (node (ref "C124") (pin "1") (pinfunction "1_1") (pintype "passive"))
    )
    (net (code "62") (name "/PCIE_PER0_P") (class "Default")
      (node (ref "C117") (pin "1") (pinfunction "1_1") (pintype "passive"))
    )
    (net (code "63") (name "/PCIE_PERST#") (class "Default")
      (node (ref "R95") (pin "1") (pinfunction "1_1") (pintype "passive"))
    )
    (net (code "64") (name "/PCIE_PET0_N") (class "Default")
      (node (ref "C115") (pin "1") (pinfunction "1_1") (pintype "passive"))
    )
    (net (code "65") (name "/PCIE_PET0_P") (class "Default")
      (node (ref "C114") (pin "1") (pinfunction "1_1") (pintype "passive"))
    )
    (net (code "66") (name "/PCIE_REF_CLK_N") (class "Default")
      (node (ref "C113") (pin "1") (pinfunction "1_1") (pintype "passive"))
    )
    (net (code "67") (name "/PCIE_REF_CLK_P") (class "Default")
      (node (ref "C112") (pin "1") (pinfunction "1_1") (pintype "passive"))
    )
    (net (code "68") (name "/PCIE_W_DISABLE2#") (class "Default")
      (node (ref "R79") (pin "1") (pinfunction "1_1") (pintype "passive"))
    )
    (net (code "69") (name "/R1_N") (class "Default")
      (node (ref "C124") (pin "2") (pinfunction "2_2") (pintype "passive"))
      (node (ref "IC6") (pin "R2") (pinfunction "SD1_RX_N_R2") (pintype "power_in"))
    )
    (net (code "70") (name "/R1_P") (class "Default")
      (node (ref "C117") (pin "2") (pinfunction "2_2") (pintype "passive"))
      (node (ref "IC6") (pin "P2") (pinfunction "SD1_RX_P_P2") (pintype "power_in"))
    )
    (net (code "71") (name "/T0_N") (class "Default")
      (node (ref "C115") (pin "2") (pinfunction "2_2") (pintype "passive"))
      (node (ref "IC6") (pin "R4") (pinfunction "SD1_TX_N_R4") (pintype "power_in"))
    )
    (net (code "72") (name "/T0_P") (class "Default")
      (node (ref "C114") (pin "2") (pinfunction "2_2") (pintype "passive"))
      (node (ref "IC6") (pin "P4") (pinfunction "SD1_TX_P_P4") (pintype "power_in"))
    )
    (net (code "73") (name "GND") (class "Default")
      (node (ref "C116") (pin "2") (pinfunction "2_2") (pintype "passive"))
      (node (ref "C118") (pin "1") (pinfunction "1_1") (pintype "passive"))
      (node (ref "C119") (pin "1") (pinfunction "1_1") (pintype "passive"))
      (node (ref "C120") (pin "1") (pinfunction "1_1") (pintype "passive"))
      (node (ref "C121") (pin "1") (pinfunction "1_1") (pintype "passive"))
      (node (ref "C122") (pin "1") (pinfunction "1_1") (pintype "passive"))
      (node (ref "C123") (pin "2") (pinfunction "2_2") (pintype "passive"))
      (node (ref "C126") (pin "1") (pinfunction "1_1") (pintype "passive"))
      (node (ref "C127") (pin "2") (pinfunction "2_2") (pintype "passive"))
      (node (ref "C128") (pin "2") (pinfunction "2_2") (pintype "passive"))
      (node (ref "C129") (pin "1") (pinfunction "1_1") (pintype "passive"))
      (node (ref "C130") (pin "1") (pinfunction "1_1") (pintype "passive"))
      (node (ref "C132") (pin "1") (pinfunction "1_1") (pintype "passive"))
      (node (ref "C133") (pin "2") (pinfunction "2_2") (pintype "passive"))
      (node (ref "C134") (pin "2") (pinfunction "2_2") (pintype "passive"))
      (node (ref "C135") (pin "1") (pinfunction "1_1") (pintype "passive"))
      (node (ref "C136") (pin "1") (pinfunction "1_1") (pintype "passive"))
      (node (ref "C137") (pin "1") (pinfunction "1_1") (pintype "passive"))
      (node (ref "C138") (pin "2") (pinfunction "2_2") (pintype "passive"))
      (node (ref "C139") (pin "1") (pinfunction "1_1") (pintype "passive"))
      (node (ref "C140") (pin "1") (pinfunction "1_1") (pintype "passive"))
      (node (ref "C141") (pin "1") (pinfunction "1_1") (pintype "passive"))
      (node (ref "C142") (pin "1") (pinfunction "1_1") (pintype "passive"))
      (node (ref "C143") (pin "1") (pinfunction "1_1") (pintype "passive"))
      (node (ref "C144") (pin "2") (pinfunction "2_2") (pintype "passive"))
      (node (ref "C145") (pin "1") (pinfunction "1_1") (pintype "passive"))
      (node (ref "C146") (pin "1") (pinfunction "1_1") (pintype "passive"))
      (node (ref "C147") (pin "1") (pinfunction "1_1") (pintype "passive"))
      (node (ref "C148") (pin "2") (pinfunction "2_2") (pintype "passive"))
      (node (ref "C149") (pin "1") (pinfunction "1_1") (pintype "passive"))
      (node (ref "C150") (pin "2") (pinfunction "2_2") (pintype "passive"))
      (node (ref "C151") (pin "2") (pinfunction "2_2") (pintype "passive"))
      (node (ref "C152") (pin "1") (pinfunction "1_1") (pintype "passive"))
      (node (ref "C153") (pin "1") (pinfunction "1_1") (pintype "passive"))
      (node (ref "C154") (pin "1") (pinfunction "1_1") (pintype "passive"))
      (node (ref "C155") (pin "1") (pinfunction "1_1") (pintype "passive"))
      (node (ref "C156") (pin "2") (pinfunction "2_2") (pintype "passive"))
      (node (ref "C157") (pin "1") (pinfunction "1_1") (pintype "passive"))
      (node (ref "C158") (pin "1") (pinfunction "1_1") (pintype "passive"))
      (node (ref "C159") (pin "1") (pinfunction "1_1") (pintype "passive"))
      (node (ref "C160") (pin "1") (pinfunction "1_1") (pintype "passive"))
      (node (ref "C161") (pin "1") (pinfunction "1_1") (pintype "passive"))
      (node (ref "C162") (pin "1") (pinfunction "1_1") (pintype "passive"))
      (node (ref "IC6") (pin "B1") (pinfunction "AFE_GND01_B1") (pintype "power_in"))
      (node (ref "IC6") (pin "B11") (pinfunction "AFE_GND04_B11") (pintype "power_in"))
      (node (ref "IC6") (pin "B13") (pinfunction "AFE_GND05_B13") (pintype "power_in"))
      (node (ref "IC6") (pin "B15") (pinfunction "AFE_GND06_B15") (pintype "power_in"))
      (node (ref "IC6") (pin "B3") (pinfunction "AFE_GND02_B3") (pintype "power_in"))
      (node (ref "IC6") (pin "B5") (pinfunction "AFE_GND03_B5") (pintype "power_in"))
      (node (ref "IC6") (pin "C10") (pinfunction "AFE_GND12_C10") (pintype "power_in"))
      (node (ref "IC6") (pin "C12") (pinfunction "AFE_GND13_C12") (pintype "power_in"))
      (node (ref "IC6") (pin "C14") (pinfunction "AFE_GND14_C14") (pintype "power_in"))
      (node (ref "IC6") (pin "C2") (pinfunction "AFE_GND07_C2") (pintype "power_in"))
      (node (ref "IC6") (pin "C4") (pinfunction "AFE_GND08_C4") (pintype "power_in"))
      (node (ref "IC6") (pin "C6") (pinfunction "AFE_GND09_C6") (pintype "power_in"))
      (node (ref "IC6") (pin "C7") (pinfunction "AFE_GND10_C7") (pintype "power_in"))
      (node (ref "IC6") (pin "C9") (pinfunction "AFE_GND11_C9") (pintype "power_in"))
      (node (ref "IC6") (pin "D10") (pinfunction "AFE_GND17_D10") (pintype "power_in"))
      (node (ref "IC6") (pin "D14") (pinfunction "AFE_GND18_D14") (pintype "power_in"))
      (node (ref "IC6") (pin "D2") (pinfunction "AFE_GND15_D2") (pintype "power_in"))
      (node (ref "IC6") (pin "D5") (pinfunction "VREF_RX_N_D5") (pintype "power_in"))
      (node (ref "IC6") (pin "D6") (pinfunction "AFE_GND16_D6") (pintype "power_in"))
      (node (ref "IC6") (pin "E1") (pinfunction "AFE_GND19_E1") (pintype "power_in"))
      (node (ref "IC6") (pin "E12") (pinfunction "AFE_GND23_E12") (pintype "power_in"))
      (node (ref "IC6") (pin "E15") (pinfunction "AFE_GND24_E15") (pintype "power_in"))
      (node (ref "IC6") (pin "E4") (pinfunction "AFE_GND20_E4") (pintype "power_in"))
      (node (ref "IC6") (pin "E7") (pinfunction "AFE_GND21_E7") (pintype "power_in"))
      (node (ref "IC6") (pin "E9") (pinfunction "AFE_GND22_E9") (pintype "power_in"))
      (node (ref "IC6") (pin "F12") (pinfunction "GND01_F12") (pintype "power_in"))
      (node (ref "IC6") (pin "F3") (pinfunction "AFE_GND25_F3") (pintype "power_in"))
      (node (ref "IC6") (pin "F4") (pinfunction "AFE_GND26_F4") (pintype "power_in"))
      (node (ref "IC6") (pin "F8") (pinfunction "AFE_GND27_F8") (pintype "power_in"))
      (node (ref "IC6") (pin "G11") (pinfunction "GND06_G11") (pintype "power_in"))
      (node (ref "IC6") (pin "G2") (pinfunction "AFE_GND28_G2") (pintype "power_in"))
      (node (ref "IC6") (pin "G3") (pinfunction "GND02_G3") (pintype "power_in"))
      (node (ref "IC6") (pin "G5") (pinfunction "GND03_G5") (pintype "power_in"))
      (node (ref "IC6") (pin "G7") (pinfunction "GND04_G7") (pintype "power_in"))
      (node (ref "IC6") (pin "G9") (pinfunction "GND05_G9") (pintype "power_in"))
      (node (ref "IC6") (pin "H1") (pinfunction "TD1_ANODE_H1") (pintype "power_in"))
      (node (ref "IC6") (pin "H12") (pinfunction "GND08_H12") (pintype "power_in"))
      (node (ref "IC6") (pin "H13") (pinfunction "LLCP_STIN_P_H13") (pintype "power_in"))
      (node (ref "IC6") (pin "H14") (pinfunction "LLCP_DIN_N_H14") (pintype "power_in"))
      (node (ref "IC6") (pin "H15") (pinfunction "LLCP_DIN_P_H15") (pintype "power_in"))
      (node (ref "IC6") (pin "H2") (pinfunction "TD1_CATHODE_H2") (pintype "power_in"))
      (node (ref "IC6") (pin "H8") (pinfunction "GND07_H8") (pintype "power_in"))
      (node (ref "IC6") (pin "J11") (pinfunction "GND14_J11") (pintype "power_in"))
      (node (ref "IC6") (pin "J13") (pinfunction "LLCP_STIN_N_J13") (pintype "power_in"))
      (node (ref "IC6") (pin "J2") (pinfunction "GND09_J2") (pintype "power_in"))
      (node (ref "IC6") (pin "J3") (pinfunction "GND10_J3") (pintype "power_in"))
      (node (ref "IC6") (pin "J5") (pinfunction "GND11_J5") (pintype "power_in"))
      (node (ref "IC6") (pin "J7") (pinfunction "GND12_J7") (pintype "power_in"))
      (node (ref "IC6") (pin "J9") (pinfunction "GND13_J9") (pintype "power_in"))
      (node (ref "IC6") (pin "K12") (pinfunction "GND16_K12") (pintype "power_in"))
      (node (ref "IC6") (pin "K2") (pinfunction "PROG_VDD_K2") (pintype "power_in"))
      (node (ref "IC6") (pin "K8") (pinfunction "GND15_K8") (pintype "power_in"))
      (node (ref "IC6") (pin "L1") (pinfunction "SD_GND1_L1") (pintype "power_in"))
      (node (ref "IC6") (pin "L11") (pinfunction "GND18_L11") (pintype "power_in"))
      (node (ref "IC6") (pin "L6") (pinfunction "SD_GND2_L6") (pintype "power_in"))
      (node (ref "IC6") (pin "L7") (pinfunction "SD_GND3_L7") (pintype "power_in"))
      (node (ref "IC6") (pin "L9") (pinfunction "GND17_L9") (pintype "power_in"))
      (node (ref "IC6") (pin "M2") (pinfunction "SD_GND4_M2") (pintype "power_in"))
      (node (ref "IC6") (pin "N2") (pinfunction "SD_GND5_N2") (pintype "power_in"))
      (node (ref "IC6") (pin "N4") (pinfunction "SD_GND6_N4") (pintype "power_in"))
      (node (ref "IC6") (pin "N6") (pinfunction "SD_GND7_N6") (pintype "power_in"))
      (node (ref "IC6") (pin "P1") (pinfunction "SD_GND8_P1") (pintype "power_in"))
      (node (ref "IC6") (pin "P3") (pinfunction "SD_GND9_P3") (pintype "power_in"))
      (node (ref "IC6") (pin "P5") (pinfunction "SD_GND10_P5") (pintype "power_in"))
      (node (ref "IC7") (pin "2") (pinfunction "GND_2") (pintype "passive"))
      (node (ref "J1") (pin "3") (pinfunction "3_3") (pintype "passive"))
      (node (ref "J1") (pin "5") (pinfunction "5_5") (pintype "passive"))
      (node (ref "J1") (pin "9") (pinfunction "9_9") (pintype "passive"))
      (node (ref "R104") (pin "2") (pinfunction "2_2") (pintype "passive"))
      (node (ref "R105") (pin "2") (pinfunction "2_2") (pintype "passive"))
      (node (ref "R106") (pin "2") (pinfunction "2_2") (pintype "passive"))
      (node (ref "R107") (pin "2") (pinfunction "2_2") (pintype "passive"))
      (node (ref "R108") (pin "2") (pinfunction "2_2") (pintype "passive"))
      (node (ref "R109") (pin "2") (pinfunction "2_2") (pintype "passive"))
      (node (ref "R110") (pin "2") (pinfunction "2_2") (pintype "passive"))
      (node (ref "R111") (pin "2") (pinfunction "2_2") (pintype "passive"))
      (node (ref "R112") (pin "2") (pinfunction "2_2") (pintype "passive"))
      (node (ref "R80") (pin "1") (pinfunction "1_1") (pintype "passive"))
      (node (ref "R88") (pin "2") (pinfunction "2_2") (pintype "passive"))
      (node (ref "R91") (pin "1") (pinfunction "1_1") (pintype "passive"))
      (node (ref "X13") (pin "1") (pinfunction "1_1") (pintype "passive"))
      (node (ref "X13") (pin "12") (pinfunction "12_12") (pintype "passive"))
      (node (ref "X13") (pin "15") (pinfunction "15_15") (pintype "passive"))
      (node (ref "X13") (pin "4") (pinfunction "4_4") (pintype "passive"))
      (node (ref "X13") (pin "7") (pinfunction "7_7") (pintype "passive"))
      (node (ref "X13") (pin "9") (pinfunction "9_9") (pintype "passive"))
      (node (ref "X13") (pin "MP1") (pinfunction "MP1_MP1") (pintype "passive"))
      (node (ref "X13") (pin "MP2") (pinfunction "MP2_MP2") (pintype "passive"))
    )
    (net (code "74") (name "Net-(C125-Pad1)") (class "Default")
      (node (ref "C125") (pin "1") (pinfunction "1_1") (pintype "passive"))
      (node (ref "R85") (pin "1") (pinfunction "1_1") (pintype "passive"))
    )
    (net (code "75") (name "Net-(C131-Pad1)") (class "Default")
      (node (ref "C131") (pin "1") (pinfunction "1_1") (pintype "passive"))
      (node (ref "R89") (pin "1") (pinfunction "1_1") (pintype "passive"))
    )
    (net (code "76") (name "Net-(IC6A-CLKOUT)") (class "Default")
      (node (ref "IC6") (pin "N13") (pinfunction "CLKOUT_N13") (pintype "power_in"))
      (node (ref "R82") (pin "2") (pinfunction "2_2") (pintype "passive"))
    )
    (net (code "77") (name "Net-(IC6A-GPIO_19_{slash}ASLEEP)") (class "Default")
      (node (ref "IC6") (pin "R12") (pinfunction "GPIO_19_/ASLEEP_R12") (pintype "power_in"))
      (node (ref "R79") (pin "2") (pinfunction "2_2") (pintype "passive"))
    )
    (net (code "78") (name "Net-(IC6A-SCAN_MODE_B)") (class "Default")
      (node (ref "IC6") (pin "M13") (pinfunction "SCAN_MODE_B_M13") (pintype "power_in"))
      (node (ref "R90") (pin "1") (pinfunction "1_1") (pintype "passive"))
    )
    (net (code "79") (name "Net-(IC6A-SD1_IMP_CAL_RX)") (class "Default")
      (node (ref "IC6") (pin "K4") (pinfunction "SD1_IMP_CAL_RX_K4") (pintype "power_in"))
      (node (ref "R84") (pin "1") (pinfunction "1_1") (pintype "passive"))
    )
    (net (code "80") (name "Net-(IC6A-SD1_IMP_CAL_TX)") (class "Default")
      (node (ref "IC6") (pin "M4") (pinfunction "SD1_IMP_CAL_TX_M4") (pintype "power_in"))
      (node (ref "R83") (pin "1") (pinfunction "1_1") (pintype "passive"))
    )
    (net (code "81") (name "Net-(IC6B-IREF_TX)") (class "Default")
      (node (ref "IC6") (pin "E8") (pinfunction "IREF_TX_E8") (pintype "power_in"))
      (node (ref "R104") (pin "1") (pinfunction "1_1") (pintype "passive"))
    )
    (net (code "82") (name "Net-(IC7-D)") (class "Default")
      (node (ref "IC7") (pin "5") (pinfunction "D_5") (pintype "passive"))
      (node (ref "R81") (pin "1") (pinfunction "1_1") (pintype "passive"))
      (node (ref "R87") (pin "2") (pinfunction "2_2") (pintype "passive"))
      (node (ref "R88") (pin "1") (pinfunction "1_1") (pintype "passive"))
    )
    (net (code "83") (name "Net-(IC7-Y)") (class "Default")
      (node (ref "C125") (pin "2") (pinfunction "2_2") (pintype "passive"))
      (node (ref "IC7") (pin "4") (pinfunction "Y_4") (pintype "passive"))
      (node (ref "R80") (pin "2") (pinfunction "2_2") (pintype "passive"))
      (node (ref "R81") (pin "2") (pinfunction "2_2") (pintype "passive"))
    )
    (net (code "84") (name "Net-(IC7-Z)") (class "Default")
      (node (ref "C131") (pin "2") (pinfunction "2_2") (pintype "passive"))
      (node (ref "IC7") (pin "3") (pinfunction "Z_3") (pintype "passive"))
      (node (ref "R91") (pin "2") (pinfunction "2_2") (pintype "passive"))
    )
    (net (code "85") (name "Net-(J1-Pad1)") (class "Default")
      (node (ref "J1") (pin "1") (pinfunction "1_1") (pintype "passive"))
      (node (ref "R72") (pin "1") (pinfunction "1_1") (pintype "passive"))
    )
    (net (code "86") (name "Net-(J1-Pad2)") (class "Default")
      (node (ref "J1") (pin "2") (pinfunction "2_2") (pintype "passive"))
      (node (ref "R73") (pin "2") (pinfunction "2_2") (pintype "passive"))
    )
    (net (code "87") (name "Net-(J1-Pad4)") (class "Default")
      (node (ref "J1") (pin "4") (pinfunction "4_4") (pintype "passive"))
      (node (ref "R74") (pin "2") (pinfunction "2_2") (pintype "passive"))
    )
    (net (code "88") (name "Net-(J1-Pad6)") (class "Default")
      (node (ref "J1") (pin "6") (pinfunction "6_6") (pintype "passive"))
      (node (ref "R75") (pin "2") (pinfunction "2_2") (pintype "passive"))
    )
    (net (code "89") (name "Net-(J1-Pad8)") (class "Default")
      (node (ref "J1") (pin "8") (pinfunction "8_8") (pintype "passive"))
      (node (ref "R76") (pin "2") (pinfunction "2_2") (pintype "passive"))
    )
    (net (code "90") (name "Net-(J1-Pad10)") (class "Default")
      (node (ref "J1") (pin "10") (pinfunction "10_10") (pintype "passive"))
      (node (ref "R77") (pin "1") (pinfunction "1_1") (pintype "passive"))
    )
    (net (code "91") (name "Net-(R82-Pad1)") (class "Default")
      (node (ref "R82") (pin "1") (pinfunction "1_1") (pintype "passive"))
      (node (ref "TP1") (pin "1") (pintype "passive"))
    )
    (net (code "92") (name "VCC0P9") (class "Default")
      (node (ref "C139") (pin "2") (pinfunction "2_2") (pintype "passive"))
      (node (ref "C140") (pin "2") (pinfunction "2_2") (pintype "passive"))
      (node (ref "C141") (pin "2") (pinfunction "2_2") (pintype "passive"))
      (node (ref "C142") (pin "2") (pinfunction "2_2") (pintype "passive"))
      (node (ref "C143") (pin "2") (pinfunction "2_2") (pintype "passive"))
      (node (ref "C144") (pin "1") (pinfunction "1_1") (pintype "passive"))
      (node (ref "C148") (pin "1") (pinfunction "1_1") (pintype "passive"))
      (node (ref "C156") (pin "1") (pinfunction "1_1") (pintype "passive"))
      (node (ref "IC6") (pin "G10") (pinfunction "VDD2_G10") (pintype "power_in"))
      (node (ref "IC6") (pin "G6") (pinfunction "VDD1_G6") (pintype "power_in"))
      (node (ref "IC6") (pin "H11") (pinfunction "VDD6_H11") (pintype "power_in"))
      (node (ref "IC6") (pin "H5") (pinfunction "VDD3_H5") (pintype "power_in"))
      (node (ref "IC6") (pin "H7") (pinfunction "VDD4_H7") (pintype "power_in"))
      (node (ref "IC6") (pin "H9") (pinfunction "VDD5_H9") (pintype "power_in"))
      (node (ref "IC6") (pin "J10") (pinfunction "VDD8_J10") (pintype "power_in"))
      (node (ref "IC6") (pin "J6") (pinfunction "VDD7_J6") (pintype "power_in"))
    )
    (net (code "93") (name "VCC0P9_AFE_CVDD") (class "Default")
      (node (ref "C148") (pin "3") (pinfunction "3_3") (pintype "passive"))
      (node (ref "C152") (pin "2") (pinfunction "2_2") (pintype "passive"))
      (node (ref "C153") (pin "2") (pinfunction "2_2") (pintype "passive"))
      (node (ref "C154") (pin "2") (pinfunction "2_2") (pintype "passive"))
      (node (ref "C155") (pin "2") (pinfunction "2_2") (pintype "passive"))
      (node (ref "IC6") (pin "F11") (pinfunction "AFE_CVDD2_F11") (pintype "power_in"))
      (node (ref "IC6") (pin "F5") (pinfunction "AFE_CVDD1_F5") (pintype "power_in"))
    )
    (net (code "94") (name "VCC0P9_AFE_SVDD") (class "Default")
      (node (ref "C149") (pin "2") (pinfunction "2_2") (pintype "passive"))
      (node (ref "C150") (pin "1") (pinfunction "1_1") (pintype "passive"))
      (node (ref "C151") (pin "1") (pinfunction "1_1") (pintype "passive"))
      (node (ref "C156") (pin "3") (pinfunction "3_3") (pintype "passive"))
      (node (ref "C157") (pin "2") (pinfunction "2_2") (pintype "passive"))
      (node (ref "C158") (pin "2") (pinfunction "2_2") (pintype "passive"))
      (node (ref "C159") (pin "2") (pinfunction "2_2") (pintype "passive"))
      (node (ref "C160") (pin "2") (pinfunction "2_2") (pintype "passive"))
      (node (ref "C161") (pin "2") (pinfunction "2_2") (pintype "passive"))
      (node (ref "C162") (pin "2") (pinfunction "2_2") (pintype "passive"))
      (node (ref "IC6") (pin "D3") (pinfunction "VREF_RX_P_D3") (pintype "power_in"))
      (node (ref "IC6") (pin "E10") (pinfunction "AFE_SVDD2_E10") (pintype "power_in"))
      (node (ref "IC6") (pin "E6") (pinfunction "AFE_SVDD1_E6") (pintype "power_in"))
      (node (ref "IC6") (pin "F7") (pinfunction "AFE_SVDD3_F7") (pintype "power_in"))
      (node (ref "IC6") (pin "F9") (pinfunction "AFE_SVDD4_F9") (pintype "power_in"))
    )
    (net (code "95") (name "VCC0P9_SD_SVDD") (class "Default")
      (node (ref "C144") (pin "3") (pinfunction "3_3") (pintype "passive"))
      (node (ref "C145") (pin "2") (pinfunction "2_2") (pintype "passive"))
      (node (ref "C146") (pin "2") (pinfunction "2_2") (pintype "passive"))
      (node (ref "C147") (pin "2") (pinfunction "2_2") (pintype "passive"))
      (node (ref "IC6") (pin "K5") (pinfunction "SD_SVDD1_K5") (pintype "power_in"))
      (node (ref "IC6") (pin "K7") (pinfunction "SD_SVDD2_K7") (pintype "power_in"))
      (node (ref "R84") (pin "2") (pinfunction "2_2") (pintype "passive"))
    )
    (net (code "96") (name "VCC1P8") (class "Default")
      (node (ref "C129") (pin "2") (pinfunction "2_2") (pintype "passive"))
      (node (ref "C130") (pin "2") (pinfunction "2_2") (pintype "passive"))
      (node (ref "C134") (pin "1") (pinfunction "1_1") (pintype "passive"))
      (node (ref "IC6") (pin "K1") (pinfunction "TH_VDD_K1") (pintype "power_in"))
      (node (ref "IC6") (pin "K11") (pinfunction "OVDD2_K11") (pintype "power_in"))
      (node (ref "IC6") (pin "K9") (pinfunction "OVDD1_K9") (pintype "power_in"))
      (node (ref "IC6") (pin "L10") (pinfunction "OVDD3_L10") (pintype "power_in"))
      (node (ref "R72") (pin "2") (pinfunction "2_2") (pintype "passive"))
      (node (ref "R86") (pin "2") (pinfunction "2_2") (pintype "passive"))
      (node (ref "R90") (pin "2") (pinfunction "2_2") (pintype "passive"))
      (node (ref "R92") (pin "1") (pinfunction "1_1") (pintype "passive"))
      (node (ref "R93") (pin "1") (pinfunction "1_1") (pintype "passive"))
      (node (ref "R94") (pin "1") (pinfunction "1_1") (pintype "passive"))
    )
    (net (code "97") (name "VCC1P8_AFE_OTVDD") (class "Default")
      (node (ref "C134") (pin "3") (pinfunction "3_3") (pintype "passive"))
      (node (ref "C135") (pin "2") (pinfunction "2_2") (pintype "passive"))
      (node (ref "C136") (pin "2") (pinfunction "2_2") (pintype "passive"))
      (node (ref "C137") (pin "2") (pinfunction "2_2") (pintype "passive"))
      (node (ref "IC6") (pin "C8") (pinfunction "AFE_OTVDD_C8") (pintype "power_in"))
      (node (ref "IC6") (pin "D11") (pinfunction "AFE_OMVDD_D11") (pintype "power_in"))
    )
    (net (code "98") (name "VCC1P8_AVDD_PLAT") (class "Default")
      (node (ref "C126") (pin "2") (pinfunction "2_2") (pintype "passive"))
      (node (ref "C127") (pin "1") (pinfunction "1_1") (pintype "passive"))
      (node (ref "C128") (pin "1") (pinfunction "1_1") (pintype "passive"))
      (node (ref "IC6") (pin "H3") (pinfunction "AVDD_PLAT_H3") (pintype "power_in"))
      (node (ref "R86") (pin "1") (pinfunction "1_1") (pintype "passive"))
    )
    (net (code "99") (name "VCC1P35") (class "Default")
      (node (ref "C116") (pin "1") (pinfunction "1_1") (pintype "passive"))
      (node (ref "R78") (pin "2") (pinfunction "2_2") (pintype "passive"))
    )
    (net (code "100") (name "VCC1P35_AVDD_SD_PLL") (class "Default")
      (node (ref "C118") (pin "2") (pinfunction "2_2") (pintype "passive"))
      (node (ref "C119") (pin "2") (pinfunction "2_2") (pintype "passive"))
      (node (ref "C123") (pin "1") (pinfunction "1_1") (pintype "passive"))
      (node (ref "IC6") (pin "L3") (pinfunction "AVDD_SD_PLL_L3") (pintype "power_in"))
      (node (ref "R78") (pin "1") (pinfunction "1_1") (pintype "passive"))
    )
    (net (code "101") (name "VCC1P35_SD_XVDD") (class "Default")
      (node (ref "C116") (pin "3") (pinfunction "3_3") (pintype "passive"))
      (node (ref "C120") (pin "2") (pinfunction "2_2") (pintype "passive"))
      (node (ref "C121") (pin "2") (pinfunction "2_2") (pintype "passive"))
      (node (ref "C122") (pin "2") (pinfunction "2_2") (pintype "passive"))
      (node (ref "IC6") (pin "M5") (pinfunction "SD_XVDD1_M5") (pintype "power_in"))
      (node (ref "IC6") (pin "M6") (pinfunction "SD_XVDD2_M6") (pintype "power_in"))
      (node (ref "R83") (pin "2") (pinfunction "2_2") (pintype "passive"))
    )
    (net (code "102") (name "VCC3P3") (class "Default")
      (node (ref "X13") (pin "8") (pinfunction "8_8") (pintype "passive"))
    )
    (net (code "103") (name "VCC3P3_CLK") (class "Default")
      (node (ref "C132") (pin "2") (pinfunction "2_2") (pintype "passive"))
      (node (ref "C133") (pin "1") (pinfunction "1_1") (pintype "passive"))
      (node (ref "IC7") (pin "1") (pinfunction "VCC_1") (pintype "passive"))
    )
    (net (code "104") (name "unconnected-(IC6B-LLCP_DOUT_N-PadG13)") (class "Default")
      (node (ref "IC6") (pin "G13") (pinfunction "LLCP_DOUT_N_G13") (pintype "power_in+no_connect"))
    )
    (net (code "105") (name "unconnected-(IC6B-LLCP_DOUT_P-PadF13)") (class "Default")
      (node (ref "IC6") (pin "F13") (pinfunction "LLCP_DOUT_P_F13") (pintype "power_in+no_connect"))
    )
    (net (code "106") (name "unconnected-(IC6B-LLCP_STOUT_N-PadF14)") (class "Default")
      (node (ref "IC6") (pin "F14") (pinfunction "LLCP_STOUT_N_F14") (pintype "power_in+no_connect"))
    )
    (net (code "107") (name "unconnected-(IC6B-LLCP_STOUT_P-PadF15)") (class "Default")
      (node (ref "IC6") (pin "F15") (pinfunction "LLCP_STOUT_P_F15") (pintype "power_in+no_connect"))
    )
    (net (code "108") (name "unconnected-(IC6B-TX_DET-PadD13)") (class "Default")
      (node (ref "IC6") (pin "D13") (pinfunction "TX_DET_D13") (pintype "power_in+no_connect"))
    )
    (net (code "109") (name "unconnected-(J1-Pad7)") (class "Default")
      (node (ref "J1") (pin "7") (pinfunction "7_7") (pintype "passive+no_connect"))
    )
  )
)
